# 2_classyTKL_ALPS_matrix.net
KiCad netlist of a schematic drawn in Altium Designer
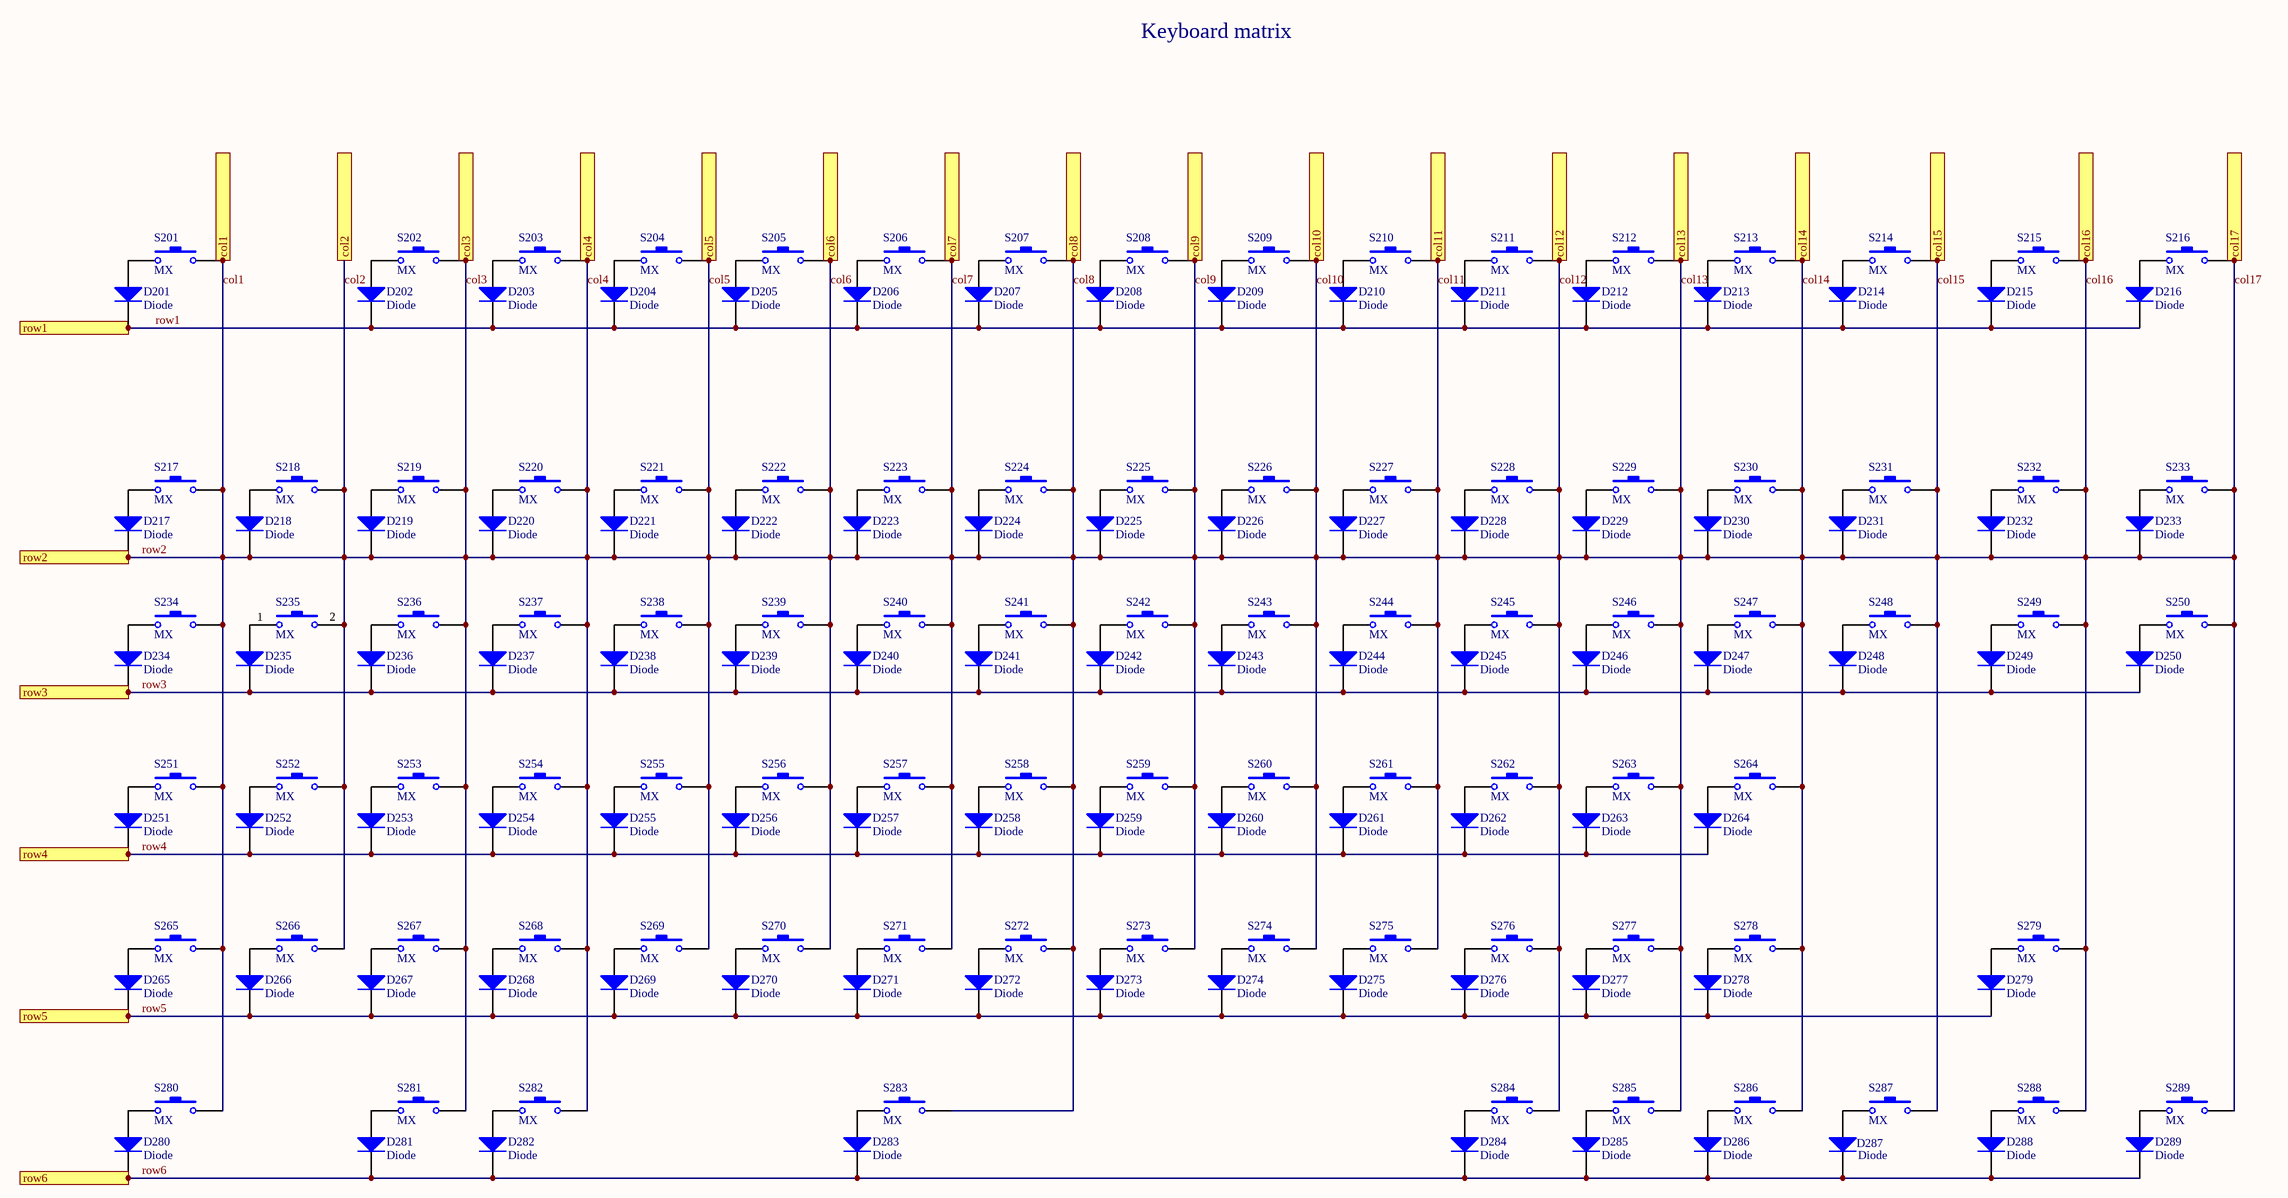
[diagram p0: 2_classyTKL_ALPS_matrix.SchDoc]

(export (version "E")
  (design (tool "Eeschema 10.0.6"))
  (components
    (comp (ref "D201")
      (value "Diode")
      (footprint "SOD-123")
      (description "Default Diode")
      (fields (field (name "LCSC PART #") "C81598") (field (name "MRF.PART") "1N4148W"))
      (libsource (lib "Miscellaneous Devices") (part "Diode"))
    )
    (comp (ref "D202")
      (value "Diode")
      (footprint "SOD-123")
      (description "Default Diode")
      (fields (field (name "LCSC PART #") "C81598") (field (name "MRF.PART") "1N4148W"))
      (libsource (lib "Miscellaneous Devices") (part "Diode"))
    )
    (comp (ref "D203")
      (value "Diode")
      (footprint "SOD-123")
      (description "Default Diode")
      (fields (field (name "LCSC PART #") "C81598") (field (name "MRF.PART") "1N4148W"))
      (libsource (lib "Miscellaneous Devices") (part "Diode"))
    )
    (comp (ref "D204")
      (value "Diode")
      (footprint "SOD-123")
      (description "Default Diode")
      (fields (field (name "LCSC PART #") "C81598") (field (name "MRF.PART") "1N4148W"))
      (libsource (lib "Miscellaneous Devices") (part "Diode"))
    )
    (comp (ref "D205")
      (value "Diode")
      (footprint "SOD-123")
      (description "Default Diode")
      (fields (field (name "LCSC PART #") "C81598") (field (name "MRF.PART") "1N4148W"))
      (libsource (lib "Miscellaneous Devices") (part "Diode"))
    )
    (comp (ref "D206")
      (value "Diode")
      (footprint "SOD-123")
      (description "Default Diode")
      (fields (field (name "LCSC PART #") "C81598") (field (name "MRF.PART") "1N4148W"))
      (libsource (lib "Miscellaneous Devices") (part "Diode"))
    )
    (comp (ref "D207")
      (value "Diode")
      (footprint "SOD-123")
      (description "Default Diode")
      (fields (field (name "LCSC PART #") "C81598") (field (name "MRF.PART") "1N4148W"))
      (libsource (lib "Miscellaneous Devices") (part "Diode"))
    )
    (comp (ref "D208")
      (value "Diode")
      (footprint "SOD-123")
      (description "Default Diode")
      (fields (field (name "LCSC PART #") "C81598") (field (name "MRF.PART") "1N4148W"))
      (libsource (lib "Miscellaneous Devices") (part "Diode"))
    )
    (comp (ref "D209")
      (value "Diode")
      (footprint "SOD-123")
      (description "Default Diode")
      (fields (field (name "LCSC PART #") "C81598") (field (name "MRF.PART") "1N4148W"))
      (libsource (lib "Miscellaneous Devices") (part "Diode"))
    )
    (comp (ref "D210")
      (value "Diode")
      (footprint "SOD-123")
      (description "Default Diode")
      (fields (field (name "LCSC PART #") "C81598") (field (name "MRF.PART") "1N4148W"))
      (libsource (lib "Miscellaneous Devices") (part "Diode"))
    )
    (comp (ref "D211")
      (value "Diode")
      (footprint "SOD-123")
      (description "Default Diode")
      (fields (field (name "LCSC PART #") "C81598") (field (name "MRF.PART") "1N4148W"))
      (libsource (lib "Miscellaneous Devices") (part "Diode"))
    )
    (comp (ref "D212")
      (value "Diode")
      (footprint "SOD-123")
      (description "Default Diode")
      (fields (field (name "LCSC PART #") "C81598") (field (name "MRF.PART") "1N4148W"))
      (libsource (lib "Miscellaneous Devices") (part "Diode"))
    )
    (comp (ref "D213")
      (value "Diode")
      (footprint "SOD-123")
      (description "Default Diode")
      (fields (field (name "LCSC PART #") "C81598") (field (name "MRF.PART") "1N4148W"))
      (libsource (lib "Miscellaneous Devices") (part "Diode"))
    )
    (comp (ref "D214")
      (value "Diode")
      (footprint "SOD-123")
      (description "Default Diode")
      (fields (field (name "LCSC PART #") "C81598") (field (name "MRF.PART") "1N4148W"))
      (libsource (lib "Miscellaneous Devices") (part "Diode"))
    )
    (comp (ref "D215")
      (value "Diode")
      (footprint "SOD-123")
      (description "Default Diode")
      (fields (field (name "LCSC PART #") "C81598") (field (name "MRF.PART") "1N4148W"))
      (libsource (lib "Miscellaneous Devices") (part "Diode"))
    )
    (comp (ref "D216")
      (value "Diode")
      (footprint "SOD-123")
      (description "Default Diode")
      (fields (field (name "LCSC PART #") "C81598") (field (name "MRF.PART") "1N4148W"))
      (libsource (lib "Miscellaneous Devices") (part "Diode"))
    )
    (comp (ref "D217")
      (value "Diode")
      (footprint "SOD-123")
      (description "Default Diode")
      (fields (field (name "LCSC PART #") "C81598") (field (name "MRF.PART") "1N4148W"))
      (libsource (lib "Miscellaneous Devices") (part "Diode"))
    )
    (comp (ref "D218")
      (value "Diode")
      (footprint "SOD-123")
      (description "Default Diode")
      (fields (field (name "LCSC PART #") "C81598") (field (name "MRF.PART") "1N4148W"))
      (libsource (lib "Miscellaneous Devices") (part "Diode"))
    )
    (comp (ref "D219")
      (value "Diode")
      (footprint "SOD-123")
      (description "Default Diode")
      (fields (field (name "LCSC PART #") "C81598") (field (name "MRF.PART") "1N4148W"))
      (libsource (lib "Miscellaneous Devices") (part "Diode"))
    )
    (comp (ref "D220")
      (value "Diode")
      (footprint "SOD-123")
      (description "Default Diode")
      (fields (field (name "LCSC PART #") "C81598") (field (name "MRF.PART") "1N4148W"))
      (libsource (lib "Miscellaneous Devices") (part "Diode"))
    )
    (comp (ref "D221")
      (value "Diode")
      (footprint "SOD-123")
      (description "Default Diode")
      (fields (field (name "LCSC PART #") "C81598") (field (name "MRF.PART") "1N4148W"))
      (libsource (lib "Miscellaneous Devices") (part "Diode"))
    )
    (comp (ref "D222")
      (value "Diode")
      (footprint "SOD-123")
      (description "Default Diode")
      (fields (field (name "LCSC PART #") "C81598") (field (name "MRF.PART") "1N4148W"))
      (libsource (lib "Miscellaneous Devices") (part "Diode"))
    )
    (comp (ref "D223")
      (value "Diode")
      (footprint "SOD-123")
      (description "Default Diode")
      (fields (field (name "LCSC PART #") "C81598") (field (name "MRF.PART") "1N4148W"))
      (libsource (lib "Miscellaneous Devices") (part "Diode"))
    )
    (comp (ref "D224")
      (value "Diode")
      (footprint "SOD-123")
      (description "Default Diode")
      (fields (field (name "LCSC PART #") "C81598") (field (name "MRF.PART") "1N4148W"))
      (libsource (lib "Miscellaneous Devices") (part "Diode"))
    )
    (comp (ref "D225")
      (value "Diode")
      (footprint "SOD-123")
      (description "Default Diode")
      (fields (field (name "LCSC PART #") "C81598") (field (name "MRF.PART") "1N4148W"))
      (libsource (lib "Miscellaneous Devices") (part "Diode"))
    )
    (comp (ref "D226")
      (value "Diode")
      (footprint "SOD-123")
      (description "Default Diode")
      (fields (field (name "LCSC PART #") "C81598") (field (name "MRF.PART") "1N4148W"))
      (libsource (lib "Miscellaneous Devices") (part "Diode"))
    )
    (comp (ref "D227")
      (value "Diode")
      (footprint "SOD-123")
      (description "Default Diode")
      (fields (field (name "LCSC PART #") "C81598") (field (name "MRF.PART") "1N4148W"))
      (libsource (lib "Miscellaneous Devices") (part "Diode"))
    )
    (comp (ref "D228")
      (value "Diode")
      (footprint "SOD-123")
      (description "Default Diode")
      (fields (field (name "LCSC PART #") "C81598") (field (name "MRF.PART") "1N4148W"))
      (libsource (lib "Miscellaneous Devices") (part "Diode"))
    )
    (comp (ref "D229")
      (value "Diode")
      (footprint "SOD-123")
      (description "Default Diode")
      (fields (field (name "LCSC PART #") "C81598") (field (name "MRF.PART") "1N4148W"))
      (libsource (lib "Miscellaneous Devices") (part "Diode"))
    )
    (comp (ref "D230")
      (value "Diode")
      (footprint "SOD-123")
      (description "Default Diode")
      (fields (field (name "LCSC PART #") "C81598") (field (name "MRF.PART") "1N4148W"))
      (libsource (lib "Miscellaneous Devices") (part "Diode"))
    )
    (comp (ref "D231")
      (value "Diode")
      (footprint "SOD-123")
      (description "Default Diode")
      (fields (field (name "LCSC PART #") "C81598") (field (name "MRF.PART") "1N4148W"))
      (libsource (lib "Miscellaneous Devices") (part "Diode"))
    )
    (comp (ref "D232")
      (value "Diode")
      (footprint "SOD-123")
      (description "Default Diode")
      (fields (field (name "LCSC PART #") "C81598") (field (name "MRF.PART") "1N4148W"))
      (libsource (lib "Miscellaneous Devices") (part "Diode"))
    )
    (comp (ref "D233")
      (value "Diode")
      (footprint "SOD-123")
      (description "Default Diode")
      (fields (field (name "LCSC PART #") "C81598") (field (name "MRF.PART") "1N4148W"))
      (libsource (lib "Miscellaneous Devices") (part "Diode"))
    )
    (comp (ref "D234")
      (value "Diode")
      (footprint "SOD-123")
      (description "Default Diode")
      (fields (field (name "LCSC PART #") "C81598") (field (name "MRF.PART") "1N4148W"))
      (libsource (lib "Miscellaneous Devices") (part "Diode"))
    )
    (comp (ref "D235")
      (value "Diode")
      (footprint "SOD-123")
      (description "Default Diode")
      (fields (field (name "LCSC PART #") "C81598") (field (name "MRF.PART") "1N4148W"))
      (libsource (lib "Miscellaneous Devices") (part "Diode"))
    )
    (comp (ref "D236")
      (value "Diode")
      (footprint "SOD-123")
      (description "Default Diode")
      (fields (field (name "LCSC PART #") "C81598") (field (name "MRF.PART") "1N4148W"))
      (libsource (lib "Miscellaneous Devices") (part "Diode"))
    )
    (comp (ref "D237")
      (value "Diode")
      (footprint "SOD-123")
      (description "Default Diode")
      (fields (field (name "LCSC PART #") "C81598") (field (name "MRF.PART") "1N4148W"))
      (libsource (lib "Miscellaneous Devices") (part "Diode"))
    )
    (comp (ref "D238")
      (value "Diode")
      (footprint "SOD-123")
      (description "Default Diode")
      (fields (field (name "LCSC PART #") "C81598") (field (name "MRF.PART") "1N4148W"))
      (libsource (lib "Miscellaneous Devices") (part "Diode"))
    )
    (comp (ref "D239")
      (value "Diode")
      (footprint "SOD-123")
      (description "Default Diode")
      (fields (field (name "LCSC PART #") "C81598") (field (name "MRF.PART") "1N4148W"))
      (libsource (lib "Miscellaneous Devices") (part "Diode"))
    )
    (comp (ref "D240")
      (value "Diode")
      (footprint "SOD-123")
      (description "Default Diode")
      (fields (field (name "LCSC PART #") "C81598") (field (name "MRF.PART") "1N4148W"))
      (libsource (lib "Miscellaneous Devices") (part "Diode"))
    )
    (comp (ref "D241")
      (value "Diode")
      (footprint "SOD-123")
      (description "Default Diode")
      (fields (field (name "LCSC PART #") "C81598") (field (name "MRF.PART") "1N4148W"))
      (libsource (lib "Miscellaneous Devices") (part "Diode"))
    )
    (comp (ref "D242")
      (value "Diode")
      (footprint "SOD-123")
      (description "Default Diode")
      (fields (field (name "LCSC PART #") "C81598") (field (name "MRF.PART") "1N4148W"))
      (libsource (lib "Miscellaneous Devices") (part "Diode"))
    )
    (comp (ref "D243")
      (value "Diode")
      (footprint "SOD-123")
      (description "Default Diode")
      (fields (field (name "LCSC PART #") "C81598") (field (name "MRF.PART") "1N4148W"))
      (libsource (lib "Miscellaneous Devices") (part "Diode"))
    )
    (comp (ref "D244")
      (value "Diode")
      (footprint "SOD-123")
      (description "Default Diode")
      (fields (field (name "LCSC PART #") "C81598") (field (name "MRF.PART") "1N4148W"))
      (libsource (lib "Miscellaneous Devices") (part "Diode"))
    )
    (comp (ref "D245")
      (value "Diode")
      (footprint "SOD-123")
      (description "Default Diode")
      (fields (field (name "LCSC PART #") "C81598") (field (name "MRF.PART") "1N4148W"))
      (libsource (lib "Miscellaneous Devices") (part "Diode"))
    )
    (comp (ref "D246")
      (value "Diode")
      (footprint "SOD-123")
      (description "Default Diode")
      (fields (field (name "LCSC PART #") "C81598") (field (name "MRF.PART") "1N4148W"))
      (libsource (lib "Miscellaneous Devices") (part "Diode"))
    )
    (comp (ref "D247")
      (value "Diode")
      (footprint "SOD-123")
      (description "Default Diode")
      (fields (field (name "LCSC PART #") "C81598") (field (name "MRF.PART") "1N4148W"))
      (libsource (lib "Miscellaneous Devices") (part "Diode"))
    )
    (comp (ref "D248")
      (value "Diode")
      (footprint "SOD-123")
      (description "Default Diode")
      (fields (field (name "LCSC PART #") "C81598") (field (name "MRF.PART") "1N4148W"))
      (libsource (lib "Miscellaneous Devices") (part "Diode"))
    )
    (comp (ref "D249")
      (value "Diode")
      (footprint "SOD-123")
      (description "Default Diode")
      (fields (field (name "LCSC PART #") "C81598") (field (name "MRF.PART") "1N4148W"))
      (libsource (lib "Miscellaneous Devices") (part "Diode"))
    )
    (comp (ref "D250")
      (value "Diode")
      (footprint "SOD-123")
      (description "Default Diode")
      (fields (field (name "LCSC PART #") "C81598") (field (name "MRF.PART") "1N4148W"))
      (libsource (lib "Miscellaneous Devices") (part "Diode"))
    )
    (comp (ref "D251")
      (value "Diode")
      (footprint "SOD-123")
      (description "Default Diode")
      (fields (field (name "LCSC PART #") "C81598") (field (name "MRF.PART") "1N4148W"))
      (libsource (lib "Miscellaneous Devices") (part "Diode"))
    )
    (comp (ref "D252")
      (value "Diode")
      (footprint "SOD-123")
      (description "Default Diode")
      (fields (field (name "LCSC PART #") "C81598") (field (name "MRF.PART") "1N4148W"))
      (libsource (lib "Miscellaneous Devices") (part "Diode"))
    )
    (comp (ref "D253")
      (value "Diode")
      (footprint "SOD-123")
      (description "Default Diode")
      (fields (field (name "LCSC PART #") "C81598") (field (name "MRF.PART") "1N4148W"))
      (libsource (lib "Miscellaneous Devices") (part "Diode"))
    )
    (comp (ref "D254")
      (value "Diode")
      (footprint "SOD-123")
      (description "Default Diode")
      (fields (field (name "LCSC PART #") "C81598") (field (name "MRF.PART") "1N4148W"))
      (libsource (lib "Miscellaneous Devices") (part "Diode"))
    )
    (comp (ref "D255")
      (value "Diode")
      (footprint "SOD-123")
      (description "Default Diode")
      (fields (field (name "LCSC PART #") "C81598") (field (name "MRF.PART") "1N4148W"))
      (libsource (lib "Miscellaneous Devices") (part "Diode"))
    )
    (comp (ref "D256")
      (value "Diode")
      (footprint "SOD-123")
      (description "Default Diode")
      (fields (field (name "LCSC PART #") "C81598") (field (name "MRF.PART") "1N4148W"))
      (libsource (lib "Miscellaneous Devices") (part "Diode"))
    )
    (comp (ref "D257")
      (value "Diode")
      (footprint "SOD-123")
      (description "Default Diode")
      (fields (field (name "LCSC PART #") "C81598") (field (name "MRF.PART") "1N4148W"))
      (libsource (lib "Miscellaneous Devices") (part "Diode"))
    )
    (comp (ref "D258")
      (value "Diode")
      (footprint "SOD-123")
      (description "Default Diode")
      (fields (field (name "LCSC PART #") "C81598") (field (name "MRF.PART") "1N4148W"))
      (libsource (lib "Miscellaneous Devices") (part "Diode"))
    )
    (comp (ref "D259")
      (value "Diode")
      (footprint "SOD-123")
      (description "Default Diode")
      (fields (field (name "LCSC PART #") "C81598") (field (name "MRF.PART") "1N4148W"))
      (libsource (lib "Miscellaneous Devices") (part "Diode"))
    )
    (comp (ref "D260")
      (value "Diode")
      (footprint "SOD-123")
      (description "Default Diode")
      (fields (field (name "LCSC PART #") "C81598") (field (name "MRF.PART") "1N4148W"))
      (libsource (lib "Miscellaneous Devices") (part "Diode"))
    )
    (comp (ref "D261")
      (value "Diode")
      (footprint "SOD-123")
      (description "Default Diode")
      (fields (field (name "LCSC PART #") "C81598") (field (name "MRF.PART") "1N4148W"))
      (libsource (lib "Miscellaneous Devices") (part "Diode"))
    )
    (comp (ref "D262")
      (value "Diode")
      (footprint "SOD-123")
      (description "Default Diode")
      (fields (field (name "LCSC PART #") "C81598") (field (name "MRF.PART") "1N4148W"))
      (libsource (lib "Miscellaneous Devices") (part "Diode"))
    )
    (comp (ref "D263")
      (value "Diode")
      (footprint "SOD-123")
      (description "Default Diode")
      (fields (field (name "LCSC PART #") "C81598") (field (name "MRF.PART") "1N4148W"))
      (libsource (lib "Miscellaneous Devices") (part "Diode"))
    )
    (comp (ref "D264")
      (value "Diode")
      (footprint "SOD-123")
      (description "Default Diode")
      (fields (field (name "LCSC PART #") "C81598") (field (name "MRF.PART") "1N4148W"))
      (libsource (lib "Miscellaneous Devices") (part "Diode"))
    )
    (comp (ref "D265")
      (value "Diode")
      (footprint "SOD-123")
      (description "Default Diode")
      (fields (field (name "LCSC PART #") "C81598") (field (name "MRF.PART") "1N4148W"))
      (libsource (lib "Miscellaneous Devices") (part "Diode"))
    )
    (comp (ref "D266")
      (value "Diode")
      (footprint "SOD-123")
      (description "Default Diode")
      (fields (field (name "LCSC PART #") "C81598") (field (name "MRF.PART") "1N4148W"))
      (libsource (lib "Miscellaneous Devices") (part "Diode"))
    )
    (comp (ref "D267")
      (value "Diode")
      (footprint "SOD-123")
      (description "Default Diode")
      (fields (field (name "LCSC PART #") "C81598") (field (name "MRF.PART") "1N4148W"))
      (libsource (lib "Miscellaneous Devices") (part "Diode"))
    )
    (comp (ref "D268")
      (value "Diode")
      (footprint "SOD-123")
      (description "Default Diode")
      (fields (field (name "LCSC PART #") "C81598") (field (name "MRF.PART") "1N4148W"))
      (libsource (lib "Miscellaneous Devices") (part "Diode"))
    )
    (comp (ref "D269")
      (value "Diode")
      (footprint "SOD-123")
      (description "Default Diode")
      (fields (field (name "LCSC PART #") "C81598") (field (name "MRF.PART") "1N4148W"))
      (libsource (lib "Miscellaneous Devices") (part "Diode"))
    )
    (comp (ref "D270")
      (value "Diode")
      (footprint "SOD-123")
      (description "Default Diode")
      (fields (field (name "LCSC PART #") "C81598") (field (name "MRF.PART") "1N4148W"))
      (libsource (lib "Miscellaneous Devices") (part "Diode"))
    )
    (comp (ref "D271")
      (value "Diode")
      (footprint "SOD-123")
      (description "Default Diode")
      (fields (field (name "LCSC PART #") "C81598") (field (name "MRF.PART") "1N4148W"))
      (libsource (lib "Miscellaneous Devices") (part "Diode"))
    )
    (comp (ref "D272")
      (value "Diode")
      (footprint "SOD-123")
      (description "Default Diode")
      (fields (field (name "LCSC PART #") "C81598") (field (name "MRF.PART") "1N4148W"))
      (libsource (lib "Miscellaneous Devices") (part "Diode"))
    )
    (comp (ref "D273")
      (value "Diode")
      (footprint "SOD-123")
      (description "Default Diode")
      (fields (field (name "LCSC PART #") "C81598") (field (name "MRF.PART") "1N4148W"))
      (libsource (lib "Miscellaneous Devices") (part "Diode"))
    )
    (comp (ref "D274")
      (value "Diode")
      (footprint "SOD-123")
      (description "Default Diode")
      (fields (field (name "LCSC PART #") "C81598") (field (name "MRF.PART") "1N4148W"))
      (libsource (lib "Miscellaneous Devices") (part "Diode"))
    )
    (comp (ref "D275")
      (value "Diode")
      (footprint "SOD-123")
      (description "Default Diode")
      (fields (field (name "LCSC PART #") "C81598") (field (name "MRF.PART") "1N4148W"))
      (libsource (lib "Miscellaneous Devices") (part "Diode"))
    )
    (comp (ref "D276")
      (value "Diode")
      (footprint "SOD-123")
      (description "Default Diode")
      (fields (field (name "LCSC PART #") "C81598") (field (name "MRF.PART") "1N4148W"))
      (libsource (lib "Miscellaneous Devices") (part "Diode"))
    )
    (comp (ref "D277")
      (value "Diode")
      (footprint "SOD-123")
      (description "Default Diode")
      (fields (field (name "LCSC PART #") "C81598") (field (name "MRF.PART") "1N4148W"))
      (libsource (lib "Miscellaneous Devices") (part "Diode"))
    )
    (comp (ref "D278")
      (value "Diode")
      (footprint "SOD-123")
      (description "Default Diode")
      (fields (field (name "LCSC PART #") "C81598") (field (name "MRF.PART") "1N4148W"))
      (libsource (lib "Miscellaneous Devices") (part "Diode"))
    )
    (comp (ref "D279")
      (value "Diode")
      (footprint "SOD-123")
      (description "Default Diode")
      (fields (field (name "LCSC PART #") "C81598") (field (name "MRF.PART") "1N4148W"))
      (libsource (lib "Miscellaneous Devices") (part "Diode"))
    )
    (comp (ref "D280")
      (value "Diode")
      (footprint "SOD-123")
      (description "Default Diode")
      (fields (field (name "LCSC PART #") "C81598") (field (name "MRF.PART") "1N4148W"))
      (libsource (lib "Miscellaneous Devices") (part "Diode"))
    )
    (comp (ref "D281")
      (value "Diode")
      (footprint "SOD-123")
      (description "Default Diode")
      (fields (field (name "LCSC PART #") "C81598") (field (name "MRF.PART") "1N4148W"))
      (libsource (lib "Miscellaneous Devices") (part "Diode"))
    )
    (comp (ref "D282")
      (value "Diode")
      (footprint "SOD-123")
      (description "Default Diode")
      (fields (field (name "LCSC PART #") "C81598") (field (name "MRF.PART") "1N4148W"))
      (libsource (lib "Miscellaneous Devices") (part "Diode"))
    )
    (comp (ref "D283")
      (value "Diode")
      (footprint "SOD-123")
      (description "Default Diode")
      (fields (field (name "LCSC PART #") "C81598") (field (name "MRF.PART") "1N4148W"))
      (libsource (lib "Miscellaneous Devices") (part "Diode"))
    )
    (comp (ref "D284")
      (value "Diode")
      (footprint "SOD-123")
      (description "Default Diode")
      (fields (field (name "LCSC PART #") "C81598") (field (name "MRF.PART") "1N4148W"))
      (libsource (lib "Miscellaneous Devices") (part "Diode"))
    )
    (comp (ref "D285")
      (value "Diode")
      (footprint "SOD-123")
      (description "Default Diode")
      (fields (field (name "LCSC PART #") "C81598") (field (name "MRF.PART") "1N4148W"))
      (libsource (lib "Miscellaneous Devices") (part "Diode"))
    )
    (comp (ref "D286")
      (value "Diode")
      (footprint "SOD-123")
      (description "Default Diode")
      (fields (field (name "LCSC PART #") "C81598") (field (name "MRF.PART") "1N4148W"))
      (libsource (lib "Miscellaneous Devices") (part "Diode"))
    )
    (comp (ref "D287")
      (value "Diode")
      (footprint "SOD-123")
      (description "Default Diode")
      (fields (field (name "LCSC PART #") "C81598") (field (name "MRF.PART") "1N4148W"))
      (libsource (lib "Miscellaneous Devices") (part "Diode"))
    )
    (comp (ref "D288")
      (value "Diode")
      (footprint "SOD-123")
      (description "Default Diode")
      (fields (field (name "LCSC PART #") "C81598") (field (name "MRF.PART") "1N4148W"))
      (libsource (lib "Miscellaneous Devices") (part "Diode"))
    )
    (comp (ref "D289")
      (value "Diode")
      (footprint "SOD-123")
      (description "Default Diode")
      (fields (field (name "LCSC PART #") "C81598") (field (name "MRF.PART") "1N4148W"))
      (libsource (lib "Miscellaneous Devices") (part "Diode"))
    )
    (comp (ref "S201")
      (value "MX")
      (footprint "Alps-switch - AEK F-row")
      (description "Switch")
      (libsource (lib "Miscellaneous Devices") (part "SW-PB"))
    )
    (comp (ref "S202")
      (value "MX")
      (footprint "Alps-switch - AEK F-row")
      (description "Switch")
      (libsource (lib "Miscellaneous Devices") (part "SW-PB"))
    )
    (comp (ref "S203")
      (value "MX")
      (footprint "Alps-switch - AEK F-row")
      (description "Switch")
      (libsource (lib "Miscellaneous Devices") (part "SW-PB"))
    )
    (comp (ref "S204")
      (value "MX")
      (footprint "Alps-switch - AEK F-row")
      (description "Switch")
      (libsource (lib "Miscellaneous Devices") (part "SW-PB"))
    )
    (comp (ref "S205")
      (value "MX")
      (footprint "Alps-switch - AEK F-row")
      (description "Switch")
      (libsource (lib "Miscellaneous Devices") (part "SW-PB"))
    )
    (comp (ref "S206")
      (value "MX")
      (footprint "Alps-switch - AEK F-row")
      (description "Switch")
      (libsource (lib "Miscellaneous Devices") (part "SW-PB"))
    )
    (comp (ref "S207")
      (value "MX")
      (footprint "Alps-switch - AEK F-row")
      (description "Switch")
      (libsource (lib "Miscellaneous Devices") (part "SW-PB"))
    )
    (comp (ref "S208")
      (value "MX")
      (footprint "Alps-switch - AEK F-row")
      (description "Switch")
      (libsource (lib "Miscellaneous Devices") (part "SW-PB"))
    )
    (comp (ref "S209")
      (value "MX")
      (footprint "Alps-switch - AEK F-row")
      (description "Switch")
      (libsource (lib "Miscellaneous Devices") (part "SW-PB"))
    )
    (comp (ref "S210")
      (value "MX")
      (footprint "Alps-switch - AEK F-row")
      (description "Switch")
      (libsource (lib "Miscellaneous Devices") (part "SW-PB"))
    )
    (comp (ref "S211")
      (value "MX")
      (footprint "Alps-switch - AEK F-row")
      (description "Switch")
      (libsource (lib "Miscellaneous Devices") (part "SW-PB"))
    )
    (comp (ref "S212")
      (value "MX")
      (footprint "Alps-switch - AEK F-row")
      (description "Switch")
      (libsource (lib "Miscellaneous Devices") (part "SW-PB"))
    )
    (comp (ref "S213")
      (value "MX")
      (footprint "Alps-switch - AEK F-row")
      (description "Switch")
      (libsource (lib "Miscellaneous Devices") (part "SW-PB"))
    )
    (comp (ref "S214")
      (value "MX")
      (footprint "Alps-switch - AEK F-row")
      (description "Switch")
      (libsource (lib "Miscellaneous Devices") (part "SW-PB"))
    )
    (comp (ref "S215")
      (value "MX")
      (footprint "Alps-switch - AEK F-row")
      (description "Switch")
      (libsource (lib "Miscellaneous Devices") (part "SW-PB"))
    )
    (comp (ref "S216")
      (value "MX")
      (footprint "Alps-switch - AEK F-row")
      (description "Switch")
      (libsource (lib "Miscellaneous Devices") (part "SW-PB"))
    )
    (comp (ref "S217")
      (value "MX")
      (footprint "Alps-switch - switched pol")
      (description "Switch")
      (libsource (lib "Miscellaneous Devices") (part "SW-PB"))
    )
    (comp (ref "S218")
      (value "MX")
      (footprint "Alps-switch - switched pol")
      (description "Switch")
      (libsource (lib "Miscellaneous Devices") (part "SW-PB"))
    )
    (comp (ref "S219")
      (value "MX")
      (footprint "Alps-switch - switched pol")
      (description "Switch")
      (libsource (lib "Miscellaneous Devices") (part "SW-PB"))
    )
    (comp (ref "S220")
      (value "MX")
      (footprint "Alps-switch - switched pol")
      (description "Switch")
      (libsource (lib "Miscellaneous Devices") (part "SW-PB"))
    )
    (comp (ref "S221")
      (value "MX")
      (footprint "Alps-switch - switched pol")
      (description "Switch")
      (libsource (lib "Miscellaneous Devices") (part "SW-PB"))
    )
    (comp (ref "S222")
      (value "MX")
      (footprint "Alps-switch - switched pol")
      (description "Switch")
      (libsource (lib "Miscellaneous Devices") (part "SW-PB"))
    )
    (comp (ref "S223")
      (value "MX")
      (footprint "Alps-switch - switched pol")
      (description "Switch")
      (libsource (lib "Miscellaneous Devices") (part "SW-PB"))
    )
    (comp (ref "S224")
      (value "MX")
      (footprint "Alps-switch - switched pol")
      (description "Switch")
      (libsource (lib "Miscellaneous Devices") (part "SW-PB"))
    )
    (comp (ref "S225")
      (value "MX")
      (footprint "Alps-switch - switched pol")
      (description "Switch")
      (libsource (lib "Miscellaneous Devices") (part "SW-PB"))
    )
    (comp (ref "S226")
      (value "MX")
      (footprint "Alps-switch - switched pol")
      (description "Switch")
      (libsource (lib "Miscellaneous Devices") (part "SW-PB"))
    )
    (comp (ref "S227")
      (value "MX")
      (footprint "Alps-switch - switched pol")
      (description "Switch")
      (libsource (lib "Miscellaneous Devices") (part "SW-PB"))
    )
    (comp (ref "S228")
      (value "MX")
      (footprint "Alps-switch - switched pol")
      (description "Switch")
      (libsource (lib "Miscellaneous Devices") (part "SW-PB"))
    )
    (comp (ref "S229")
      (value "MX")
      (footprint "Alps-switch - switched pol")
      (description "Switch")
      (libsource (lib "Miscellaneous Devices") (part "SW-PB"))
    )
    (comp (ref "S230")
      (value "MX")
      (footprint "Alps-switch")
      (description "Switch")
      (libsource (lib "Miscellaneous Devices") (part "SW-PB"))
    )
    (comp (ref "S231")
      (value "MX")
      (footprint "Alps-switch")
      (description "Switch")
      (libsource (lib "Miscellaneous Devices") (part "SW-PB"))
    )
    (comp (ref "S232")
      (value "MX")
      (footprint "Alps-switch")
      (description "Switch")
      (libsource (lib "Miscellaneous Devices") (part "SW-PB"))
    )
    (comp (ref "S233")
      (value "MX")
      (footprint "Alps-switch")
      (description "Switch")
      (libsource (lib "Miscellaneous Devices") (part "SW-PB"))
    )
    (comp (ref "S234")
      (value "MX")
      (footprint "ALPS-switch - 1.5U")
      (description "TAB")
      (libsource (lib "Miscellaneous Devices") (part "SW-PB"))
    )
    (comp (ref "S235")
      (value "MX")
      (footprint "Alps-switch - switched pol")
      (description "Switch")
      (libsource (lib "") (part "SW-PB_1"))
    )
    (comp (ref "S236")
      (value "MX")
      (footprint "Alps-switch - switched pol")
      (description "Switch")
      (libsource (lib "Miscellaneous Devices") (part "SW-PB"))
    )
    (comp (ref "S237")
      (value "MX")
      (footprint "Alps-switch - switched pol")
      (description "Switch")
      (libsource (lib "Miscellaneous Devices") (part "SW-PB"))
    )
    (comp (ref "S238")
      (value "MX")
      (footprint "Alps-switch - switched pol")
      (description "Switch")
      (libsource (lib "Miscellaneous Devices") (part "SW-PB"))
    )
    (comp (ref "S239")
      (value "MX")
      (footprint "Alps-switch - switched pol")
      (description "Switch")
      (libsource (lib "Miscellaneous Devices") (part "SW-PB"))
    )
    (comp (ref "S240")
      (value "MX")
      (footprint "Alps-switch - switched pol")
      (description "Switch")
      (libsource (lib "Miscellaneous Devices") (part "SW-PB"))
    )
    (comp (ref "S241")
      (value "MX")
      (footprint "Alps-switch - switched pol")
      (description "Switch")
      (libsource (lib "Miscellaneous Devices") (part "SW-PB"))
    )
    (comp (ref "S242")
      (value "MX")
      (footprint "Alps-switch - switched pol")
      (description "Switch")
      (libsource (lib "Miscellaneous Devices") (part "SW-PB"))
    )
    (comp (ref "S243")
      (value "MX")
      (footprint "Alps-switch - switched pol")
      (description "Switch")
      (libsource (lib "Miscellaneous Devices") (part "SW-PB"))
    )
    (comp (ref "S244")
      (value "MX")
      (footprint "Alps-switch - switched pol")
      (description "Switch")
      (libsource (lib "Miscellaneous Devices") (part "SW-PB"))
    )
    (comp (ref "S245")
      (value "MX")
      (footprint "Alps-switch - switched pol")
      (description "Switch")
      (libsource (lib "Miscellaneous Devices") (part "SW-PB"))
    )
    (comp (ref "S246")
      (value "MX")
      (footprint "Alps-switch - switched pol")
      (description "Switch")
      (libsource (lib "Miscellaneous Devices") (part "SW-PB"))
    )
    (comp (ref "S247")
      (value "MX")
      (footprint "ALPS-SWITCH - PIPE_ISO_ENTER")
      (description "Switch")
      (libsource (lib "Miscellaneous Devices") (part "SW-PB"))
    )
    (comp (ref "S248")
      (value "MX")
      (footprint "Alps-switch")
      (description "Switch")
      (libsource (lib "Miscellaneous Devices") (part "SW-PB"))
    )
    (comp (ref "S249")
      (value "MX")
      (footprint "Alps-switch")
      (description "Switch")
      (libsource (lib "Miscellaneous Devices") (part "SW-PB"))
    )
    (comp (ref "S250")
      (value "MX")
      (footprint "Alps-switch")
      (description "Switch")
      (libsource (lib "Miscellaneous Devices") (part "SW-PB"))
    )
    (comp (ref "S251")
      (value "MX")
      (footprint "ALPS-switch - CAPS")
      (description "Switch")
      (libsource (lib "Miscellaneous Devices") (part "SW-PB"))
    )
    (comp (ref "S252")
      (value "MX")
      (footprint "Alps-switch - switched pol")
      (description "Switch")
      (libsource (lib "Miscellaneous Devices") (part "SW-PB"))
    )
    (comp (ref "S253")
      (value "MX")
      (footprint "Alps-switch - switched pol")
      (description "Switch")
      (libsource (lib "Miscellaneous Devices") (part "SW-PB"))
    )
    (comp (ref "S254")
      (value "MX")
      (footprint "Alps-switch - switched pol")
      (description "Switch")
      (libsource (lib "Miscellaneous Devices") (part "SW-PB"))
    )
    (comp (ref "S255")
      (value "MX")
      (footprint "Alps-switch - switched pol")
      (description "Switch")
      (libsource (lib "Miscellaneous Devices") (part "SW-PB"))
    )
    (comp (ref "S256")
      (value "MX")
      (footprint "Alps-switch - switched pol")
      (description "Switch")
      (libsource (lib "Miscellaneous Devices") (part "SW-PB"))
    )
    (comp (ref "S257")
      (value "MX")
      (footprint "Alps-switch - switched pol")
      (description "Switch")
      (libsource (lib "Miscellaneous Devices") (part "SW-PB"))
    )
    (comp (ref "S258")
      (value "MX")
      (footprint "Alps-switch - switched pol")
      (description "Switch")
      (libsource (lib "Miscellaneous Devices") (part "SW-PB"))
    )
    (comp (ref "S259")
      (value "MX")
      (footprint "Alps-switch - switched pol")
      (description "Switch")
      (libsource (lib "Miscellaneous Devices") (part "SW-PB"))
    )
    (comp (ref "S260")
      (value "MX")
      (footprint "Alps-switch - switched pol")
      (description "Switch")
      (libsource (lib "Miscellaneous Devices") (part "SW-PB"))
    )
    (comp (ref "S261")
      (value "MX")
      (footprint "Alps-switch - switched pol")
      (description "Switch")
      (libsource (lib "Miscellaneous Devices") (part "SW-PB"))
    )
    (comp (ref "S262")
      (value "MX")
      (footprint "Alps-switch - switched pol")
      (description "Switch")
      (libsource (lib "Miscellaneous Devices") (part "SW-PB"))
    )
    (comp (ref "S263")
      (value "MX")
      (footprint "ALPS-SWITCH - ENTER_ANSI_ISO_KEY")
      (description "Switch")
      (libsource (lib "Miscellaneous Devices") (part "SW-PB"))
    )
    (comp (ref "S264")
      (value "MX")
      (footprint "ALPS-switch - backspace")
      (description "Switch")
      (libsource (lib "Miscellaneous Devices") (part "SW-PB"))
    )
    (comp (ref "S265")
      (value "MX")
      (footprint "ALPS-switch - Left shift V2")
      (description "Switch")
      (libsource (lib "Miscellaneous Devices") (part "SW-PB"))
    )
    (comp (ref "S266")
      (value "MX")
      (footprint "Alps-switch - switched pol")
      (description "Switch")
      (libsource (lib "Miscellaneous Devices") (part "SW-PB"))
    )
    (comp (ref "S267")
      (value "MX")
      (footprint "Alps-switch - switched pol")
      (description "Switch")
      (libsource (lib "Miscellaneous Devices") (part "SW-PB"))
    )
    (comp (ref "S268")
      (value "MX")
      (footprint "Alps-switch - switched pol")
      (description "Switch")
      (libsource (lib "Miscellaneous Devices") (part "SW-PB"))
    )
    (comp (ref "S269")
      (value "MX")
      (footprint "Alps-switch - switched pol")
      (description "Switch")
      (libsource (lib "Miscellaneous Devices") (part "SW-PB"))
    )
    (comp (ref "S270")
      (value "MX")
      (footprint "Alps-switch - switched pol")
      (description "Switch")
      (libsource (lib "Miscellaneous Devices") (part "SW-PB"))
    )
    (comp (ref "S271")
      (value "MX")
      (footprint "Alps-switch - switched pol")
      (description "Switch")
      (libsource (lib "Miscellaneous Devices") (part "SW-PB"))
    )
    (comp (ref "S272")
      (value "MX")
      (footprint "Alps-switch - switched pol")
      (description "Switch")
      (libsource (lib "Miscellaneous Devices") (part "SW-PB"))
    )
    (comp (ref "S273")
      (value "MX")
      (footprint "Alps-switch - switched pol")
      (description "Switch")
      (libsource (lib "Miscellaneous Devices") (part "SW-PB"))
    )
    (comp (ref "S274")
      (value "MX")
      (footprint "Alps-switch - switched pol")
      (description "Switch")
      (libsource (lib "Miscellaneous Devices") (part "SW-PB"))
    )
    (comp (ref "S275")
      (value "MX")
      (footprint "Alps-switch - switched pol")
      (description "Switch")
      (libsource (lib "Miscellaneous Devices") (part "SW-PB"))
    )
    (comp (ref "S276")
      (value "MX")
      (footprint "Alps-switch - switched pol")
      (description "Switch")
      (libsource (lib "Miscellaneous Devices") (part "SW-PB"))
    )
    (comp (ref "S277")
      (value "MX")
      (footprint "ALPS-switch - right shift V2")
      (description "Switch")
      (libsource (lib "Miscellaneous Devices") (part "SW-PB"))
    )
    (comp (ref "S278")
      (value "MX")
      (footprint "Alps-switch - switched pol")
      (description "Switch")
      (libsource (lib "Miscellaneous Devices") (part "SW-PB"))
    )
    (comp (ref "S279")
      (value "MX")
      (footprint "Alps-switch")
      (description "Switch")
      (libsource (lib "Miscellaneous Devices") (part "SW-PB"))
    )
    (comp (ref "S280")
      (value "MX")
      (footprint "ALPS-switch - 1.5U")
      (description "Switch")
      (libsource (lib "Miscellaneous Devices") (part "SW-PB"))
    )
    (comp (ref "S281")
      (value "MX")
      (footprint "Alps-switch")
      (description "Switch")
      (libsource (lib "Miscellaneous Devices") (part "SW-PB"))
    )
    (comp (ref "S282")
      (value "MX")
      (footprint "ALPS-switch - 1.5U")
      (description "Switch")
      (libsource (lib "Miscellaneous Devices") (part "SW-PB"))
    )
    (comp (ref "S283")
      (value "MX")
      (footprint "ALPS-switch - 7u space")
      (description "Switch")
      (libsource (lib "Miscellaneous Devices") (part "SW-PB"))
    )
    (comp (ref "S284")
      (value "MX")
      (footprint "ALPS-switch - 1.5U")
      (description "Switch")
      (libsource (lib "Miscellaneous Devices") (part "SW-PB"))
    )
    (comp (ref "S285")
      (value "MX")
      (footprint "Alps-switch")
      (description "Switch")
      (libsource (lib "Miscellaneous Devices") (part "SW-PB"))
    )
    (comp (ref "S286")
      (value "MX")
      (footprint "ALPS-switch - 1.5U")
      (description "Switch")
      (libsource (lib "Miscellaneous Devices") (part "SW-PB"))
    )
    (comp (ref "S287")
      (value "MX")
      (footprint "Alps-switch")
      (description "Switch")
      (libsource (lib "Miscellaneous Devices") (part "SW-PB"))
    )
    (comp (ref "S288")
      (value "MX")
      (footprint "Alps-switch")
      (description "Switch")
      (libsource (lib "Miscellaneous Devices") (part "SW-PB"))
    )
    (comp (ref "S289")
      (value "MX")
      (footprint "Alps-switch")
      (description "Switch")
      (libsource (lib "Miscellaneous Devices") (part "SW-PB"))
    )
  )
  (nets
    (net (code "1") (name "/col1") (class "Default")
      (node (ref "D217") (pin "2") (pinfunction "K_2") (pintype "passive"))
      (node (ref "D218") (pin "2") (pinfunction "K_2") (pintype "passive"))
      (node (ref "D219") (pin "2") (pinfunction "K_2") (pintype "passive"))
      (node (ref "D220") (pin "2") (pinfunction "K_2") (pintype "passive"))
      (node (ref "D221") (pin "2") (pinfunction "K_2") (pintype "passive"))
      (node (ref "D222") (pin "2") (pinfunction "K_2") (pintype "passive"))
      (node (ref "D223") (pin "2") (pinfunction "K_2") (pintype "passive"))
      (node (ref "D224") (pin "2") (pinfunction "K_2") (pintype "passive"))
      (node (ref "D225") (pin "2") (pinfunction "K_2") (pintype "passive"))
      (node (ref "D226") (pin "2") (pinfunction "K_2") (pintype "passive"))
      (node (ref "D227") (pin "2") (pinfunction "K_2") (pintype "passive"))
      (node (ref "D228") (pin "2") (pinfunction "K_2") (pintype "passive"))
      (node (ref "D229") (pin "2") (pinfunction "K_2") (pintype "passive"))
      (node (ref "D230") (pin "2") (pinfunction "K_2") (pintype "passive"))
      (node (ref "D231") (pin "2") (pinfunction "K_2") (pintype "passive"))
      (node (ref "D232") (pin "2") (pinfunction "K_2") (pintype "passive"))
      (node (ref "D233") (pin "2") (pinfunction "K_2") (pintype "passive"))
      (node (ref "S201") (pin "2") (pinfunction "2_2") (pintype "passive"))
      (node (ref "S202") (pin "2") (pinfunction "2_2") (pintype "passive"))
      (node (ref "S203") (pin "2") (pinfunction "2_2") (pintype "passive"))
      (node (ref "S204") (pin "2") (pinfunction "2_2") (pintype "passive"))
      (node (ref "S205") (pin "2") (pinfunction "2_2") (pintype "passive"))
      (node (ref "S206") (pin "2") (pinfunction "2_2") (pintype "passive"))
      (node (ref "S207") (pin "2") (pinfunction "2_2") (pintype "passive"))
      (node (ref "S208") (pin "2") (pinfunction "2_2") (pintype "passive"))
      (node (ref "S209") (pin "2") (pinfunction "2_2") (pintype "passive"))
      (node (ref "S210") (pin "2") (pinfunction "2_2") (pintype "passive"))
      (node (ref "S211") (pin "2") (pinfunction "2_2") (pintype "passive"))
      (node (ref "S212") (pin "2") (pinfunction "2_2") (pintype "passive"))
      (node (ref "S213") (pin "2") (pinfunction "2_2") (pintype "passive"))
      (node (ref "S214") (pin "2") (pinfunction "2_2") (pintype "passive"))
      (node (ref "S215") (pin "2") (pinfunction "2_2") (pintype "passive"))
      (node (ref "S216") (pin "2") (pinfunction "2_2") (pintype "passive"))
      (node (ref "S217") (pin "2") (pinfunction "2_2") (pintype "passive"))
      (node (ref "S218") (pin "2") (pinfunction "2_2") (pintype "passive"))
      (node (ref "S219") (pin "2") (pinfunction "2_2") (pintype "passive"))
      (node (ref "S220") (pin "2") (pinfunction "2_2") (pintype "passive"))
      (node (ref "S221") (pin "2") (pinfunction "2_2") (pintype "passive"))
      (node (ref "S222") (pin "2") (pinfunction "2_2") (pintype "passive"))
      (node (ref "S223") (pin "2") (pinfunction "2_2") (pintype "passive"))
      (node (ref "S224") (pin "2") (pinfunction "2_2") (pintype "passive"))
      (node (ref "S225") (pin "2") (pinfunction "2_2") (pintype "passive"))
      (node (ref "S226") (pin "2") (pinfunction "2_2") (pintype "passive"))
      (node (ref "S227") (pin "2") (pinfunction "2_2") (pintype "passive"))
      (node (ref "S228") (pin "2") (pinfunction "2_2") (pintype "passive"))
      (node (ref "S229") (pin "2") (pinfunction "2_2") (pintype "passive"))
      (node (ref "S230") (pin "2") (pinfunction "2_2") (pintype "passive"))
      (node (ref "S231") (pin "2") (pinfunction "2_2") (pintype "passive"))
      (node (ref "S232") (pin "2") (pinfunction "2_2") (pintype "passive"))
      (node (ref "S233") (pin "2") (pinfunction "2_2") (pintype "passive"))
      (node (ref "S234") (pin "2") (pinfunction "2_2") (pintype "passive"))
      (node (ref "S235") (pin "2") (pinfunction "2_2") (pintype "passive"))
      (node (ref "S236") (pin "2") (pinfunction "2_2") (pintype "passive"))
      (node (ref "S237") (pin "2") (pinfunction "2_2") (pintype "passive"))
      (node (ref "S238") (pin "2") (pinfunction "2_2") (pintype "passive"))
      (node (ref "S239") (pin "2") (pinfunction "2_2") (pintype "passive"))
      (node (ref "S240") (pin "2") (pinfunction "2_2") (pintype "passive"))
      (node (ref "S241") (pin "2") (pinfunction "2_2") (pintype "passive"))
      (node (ref "S242") (pin "2") (pinfunction "2_2") (pintype "passive"))
      (node (ref "S243") (pin "2") (pinfunction "2_2") (pintype "passive"))
      (node (ref "S244") (pin "2") (pinfunction "2_2") (pintype "passive"))
      (node (ref "S245") (pin "2") (pinfunction "2_2") (pintype "passive"))
      (node (ref "S246") (pin "2") (pinfunction "2_2") (pintype "passive"))
      (node (ref "S247") (pin "2") (pinfunction "2_2") (pintype "passive"))
      (node (ref "S248") (pin "2") (pinfunction "2_2") (pintype "passive"))
      (node (ref "S249") (pin "2") (pinfunction "2_2") (pintype "passive"))
      (node (ref "S250") (pin "2") (pinfunction "2_2") (pintype "passive"))
      (node (ref "S251") (pin "2") (pinfunction "2_2") (pintype "passive"))
      (node (ref "S252") (pin "2") (pinfunction "2_2") (pintype "passive"))
      (node (ref "S253") (pin "2") (pinfunction "2_2") (pintype "passive"))
      (node (ref "S254") (pin "2") (pinfunction "2_2") (pintype "passive"))
      (node (ref "S255") (pin "2") (pinfunction "2_2") (pintype "passive"))
      (node (ref "S256") (pin "2") (pinfunction "2_2") (pintype "passive"))
      (node (ref "S257") (pin "2") (pinfunction "2_2") (pintype "passive"))
      (node (ref "S258") (pin "2") (pinfunction "2_2") (pintype "passive"))
      (node (ref "S259") (pin "2") (pinfunction "2_2") (pintype "passive"))
      (node (ref "S260") (pin "2") (pinfunction "2_2") (pintype "passive"))
      (node (ref "S261") (pin "2") (pinfunction "2_2") (pintype "passive"))
      (node (ref "S262") (pin "2") (pinfunction "2_2") (pintype "passive"))
      (node (ref "S263") (pin "2") (pinfunction "2_2") (pintype "passive"))
      (node (ref "S264") (pin "2") (pinfunction "2_2") (pintype "passive"))
      (node (ref "S265") (pin "2") (pinfunction "2_2") (pintype "passive"))
      (node (ref "S266") (pin "2") (pinfunction "2_2") (pintype "passive"))
      (node (ref "S267") (pin "2") (pinfunction "2_2") (pintype "passive"))
      (node (ref "S268") (pin "2") (pinfunction "2_2") (pintype "passive"))
      (node (ref "S269") (pin "2") (pinfunction "2_2") (pintype "passive"))
      (node (ref "S270") (pin "2") (pinfunction "2_2") (pintype "passive"))
      (node (ref "S271") (pin "2") (pinfunction "2_2") (pintype "passive"))
      (node (ref "S272") (pin "2") (pinfunction "2_2") (pintype "passive"))
      (node (ref "S273") (pin "2") (pinfunction "2_2") (pintype "passive"))
      (node (ref "S274") (pin "2") (pinfunction "2_2") (pintype "passive"))
      (node (ref "S275") (pin "2") (pinfunction "2_2") (pintype "passive"))
      (node (ref "S276") (pin "2") (pinfunction "2_2") (pintype "passive"))
      (node (ref "S277") (pin "2") (pinfunction "2_2") (pintype "passive"))
      (node (ref "S278") (pin "2") (pinfunction "2_2") (pintype "passive"))
      (node (ref "S279") (pin "2") (pinfunction "2_2") (pintype "passive"))
      (node (ref "S280") (pin "2") (pinfunction "2_2") (pintype "passive"))
      (node (ref "S281") (pin "2") (pinfunction "2_2") (pintype "passive"))
      (node (ref "S282") (pin "2") (pinfunction "2_2") (pintype "passive"))
      (node (ref "S283") (pin "2") (pinfunction "2_2") (pintype "passive"))
      (node (ref "S284") (pin "2") (pinfunction "2_2") (pintype "passive"))
      (node (ref "S285") (pin "2") (pinfunction "2_2") (pintype "passive"))
      (node (ref "S286") (pin "2") (pinfunction "2_2") (pintype "passive"))
      (node (ref "S287") (pin "2") (pinfunction "2_2") (pintype "passive"))
      (node (ref "S288") (pin "2") (pinfunction "2_2") (pintype "passive"))
      (node (ref "S289") (pin "2") (pinfunction "2_2") (pintype "passive"))
    )
    (net (code "2") (name "/row1") (class "Default")
      (node (ref "D201") (pin "2") (pinfunction "K_2") (pintype "passive"))
      (node (ref "D202") (pin "2") (pinfunction "K_2") (pintype "passive"))
      (node (ref "D203") (pin "2") (pinfunction "K_2") (pintype "passive"))
      (node (ref "D204") (pin "2") (pinfunction "K_2") (pintype "passive"))
      (node (ref "D205") (pin "2") (pinfunction "K_2") (pintype "passive"))
      (node (ref "D206") (pin "2") (pinfunction "K_2") (pintype "passive"))
      (node (ref "D207") (pin "2") (pinfunction "K_2") (pintype "passive"))
      (node (ref "D208") (pin "2") (pinfunction "K_2") (pintype "passive"))
      (node (ref "D209") (pin "2") (pinfunction "K_2") (pintype "passive"))
      (node (ref "D210") (pin "2") (pinfunction "K_2") (pintype "passive"))
      (node (ref "D211") (pin "2") (pinfunction "K_2") (pintype "passive"))
      (node (ref "D212") (pin "2") (pinfunction "K_2") (pintype "passive"))
      (node (ref "D213") (pin "2") (pinfunction "K_2") (pintype "passive"))
      (node (ref "D214") (pin "2") (pinfunction "K_2") (pintype "passive"))
      (node (ref "D215") (pin "2") (pinfunction "K_2") (pintype "passive"))
      (node (ref "D216") (pin "2") (pinfunction "K_2") (pintype "passive"))
    )
    (net (code "3") (name "/row3") (class "Default")
      (node (ref "D234") (pin "2") (pinfunction "K_2") (pintype "passive"))
      (node (ref "D235") (pin "2") (pinfunction "K_2") (pintype "passive"))
      (node (ref "D236") (pin "2") (pinfunction "K_2") (pintype "passive"))
      (node (ref "D237") (pin "2") (pinfunction "K_2") (pintype "passive"))
      (node (ref "D238") (pin "2") (pinfunction "K_2") (pintype "passive"))
      (node (ref "D239") (pin "2") (pinfunction "K_2") (pintype "passive"))
      (node (ref "D240") (pin "2") (pinfunction "K_2") (pintype "passive"))
      (node (ref "D241") (pin "2") (pinfunction "K_2") (pintype "passive"))
      (node (ref "D242") (pin "2") (pinfunction "K_2") (pintype "passive"))
      (node (ref "D243") (pin "2") (pinfunction "K_2") (pintype "passive"))
      (node (ref "D244") (pin "2") (pinfunction "K_2") (pintype "passive"))
      (node (ref "D245") (pin "2") (pinfunction "K_2") (pintype "passive"))
      (node (ref "D246") (pin "2") (pinfunction "K_2") (pintype "passive"))
      (node (ref "D247") (pin "2") (pinfunction "K_2") (pintype "passive"))
      (node (ref "D248") (pin "2") (pinfunction "K_2") (pintype "passive"))
      (node (ref "D249") (pin "2") (pinfunction "K_2") (pintype "passive"))
      (node (ref "D250") (pin "2") (pinfunction "K_2") (pintype "passive"))
    )
    (net (code "4") (name "/row4") (class "Default")
      (node (ref "D251") (pin "2") (pinfunction "K_2") (pintype "passive"))
      (node (ref "D252") (pin "2") (pinfunction "K_2") (pintype "passive"))
      (node (ref "D253") (pin "2") (pinfunction "K_2") (pintype "passive"))
      (node (ref "D254") (pin "2") (pinfunction "K_2") (pintype "passive"))
      (node (ref "D255") (pin "2") (pinfunction "K_2") (pintype "passive"))
      (node (ref "D256") (pin "2") (pinfunction "K_2") (pintype "passive"))
      (node (ref "D257") (pin "2") (pinfunction "K_2") (pintype "passive"))
      (node (ref "D258") (pin "2") (pinfunction "K_2") (pintype "passive"))
      (node (ref "D259") (pin "2") (pinfunction "K_2") (pintype "passive"))
      (node (ref "D260") (pin "2") (pinfunction "K_2") (pintype "passive"))
      (node (ref "D261") (pin "2") (pinfunction "K_2") (pintype "passive"))
      (node (ref "D262") (pin "2") (pinfunction "K_2") (pintype "passive"))
      (node (ref "D263") (pin "2") (pinfunction "K_2") (pintype "passive"))
      (node (ref "D264") (pin "2") (pinfunction "K_2") (pintype "passive"))
    )
    (net (code "5") (name "/row5") (class "Default")
      (node (ref "D265") (pin "2") (pinfunction "K_2") (pintype "passive"))
      (node (ref "D266") (pin "2") (pinfunction "K_2") (pintype "passive"))
      (node (ref "D267") (pin "2") (pinfunction "K_2") (pintype "passive"))
      (node (ref "D268") (pin "2") (pinfunction "K_2") (pintype "passive"))
      (node (ref "D269") (pin "2") (pinfunction "K_2") (pintype "passive"))
      (node (ref "D270") (pin "2") (pinfunction "K_2") (pintype "passive"))
      (node (ref "D271") (pin "2") (pinfunction "K_2") (pintype "passive"))
      (node (ref "D272") (pin "2") (pinfunction "K_2") (pintype "passive"))
      (node (ref "D273") (pin "2") (pinfunction "K_2") (pintype "passive"))
      (node (ref "D274") (pin "2") (pinfunction "K_2") (pintype "passive"))
      (node (ref "D275") (pin "2") (pinfunction "K_2") (pintype "passive"))
      (node (ref "D276") (pin "2") (pinfunction "K_2") (pintype "passive"))
      (node (ref "D277") (pin "2") (pinfunction "K_2") (pintype "passive"))
      (node (ref "D278") (pin "2") (pinfunction "K_2") (pintype "passive"))
      (node (ref "D279") (pin "2") (pinfunction "K_2") (pintype "passive"))
    )
    (net (code "6") (name "/row6") (class "Default")
      (node (ref "D280") (pin "2") (pinfunction "K_2") (pintype "passive"))
      (node (ref "D281") (pin "2") (pinfunction "K_2") (pintype "passive"))
      (node (ref "D282") (pin "2") (pinfunction "K_2") (pintype "passive"))
      (node (ref "D283") (pin "2") (pinfunction "K_2") (pintype "passive"))
      (node (ref "D284") (pin "2") (pinfunction "K_2") (pintype "passive"))
      (node (ref "D285") (pin "2") (pinfunction "K_2") (pintype "passive"))
      (node (ref "D286") (pin "2") (pinfunction "K_2") (pintype "passive"))
      (node (ref "D287") (pin "2") (pinfunction "K_2") (pintype "passive"))
      (node (ref "D288") (pin "2") (pinfunction "K_2") (pintype "passive"))
      (node (ref "D289") (pin "2") (pinfunction "K_2") (pintype "passive"))
    )
    (net (code "7") (name "Net-(D201-A)") (class "Default")
      (node (ref "D201") (pin "1") (pinfunction "A_1") (pintype "passive"))
      (node (ref "S201") (pin "1") (pinfunction "1_1") (pintype "passive"))
    )
    (net (code "8") (name "Net-(D202-A)") (class "Default")
      (node (ref "D202") (pin "1") (pinfunction "A_1") (pintype "passive"))
      (node (ref "S202") (pin "1") (pinfunction "1_1") (pintype "passive"))
    )
    (net (code "9") (name "Net-(D203-A)") (class "Default")
      (node (ref "D203") (pin "1") (pinfunction "A_1") (pintype "passive"))
      (node (ref "S203") (pin "1") (pinfunction "1_1") (pintype "passive"))
    )
    (net (code "10") (name "Net-(D204-A)") (class "Default")
      (node (ref "D204") (pin "1") (pinfunction "A_1") (pintype "passive"))
      (node (ref "S204") (pin "1") (pinfunction "1_1") (pintype "passive"))
    )
    (net (code "11") (name "Net-(D205-A)") (class "Default")
      (node (ref "D205") (pin "1") (pinfunction "A_1") (pintype "passive"))
      (node (ref "S205") (pin "1") (pinfunction "1_1") (pintype "passive"))
    )
    (net (code "12") (name "Net-(D206-A)") (class "Default")
      (node (ref "D206") (pin "1") (pinfunction "A_1") (pintype "passive"))
      (node (ref "S206") (pin "1") (pinfunction "1_1") (pintype "passive"))
    )
    (net (code "13") (name "Net-(D207-A)") (class "Default")
      (node (ref "D207") (pin "1") (pinfunction "A_1") (pintype "passive"))
      (node (ref "S207") (pin "1") (pinfunction "1_1") (pintype "passive"))
    )
    (net (code "14") (name "Net-(D208-A)") (class "Default")
      (node (ref "D208") (pin "1") (pinfunction "A_1") (pintype "passive"))
      (node (ref "S208") (pin "1") (pinfunction "1_1") (pintype "passive"))
    )
    (net (code "15") (name "Net-(D209-A)") (class "Default")
      (node (ref "D209") (pin "1") (pinfunction "A_1") (pintype "passive"))
      (node (ref "S209") (pin "1") (pinfunction "1_1") (pintype "passive"))
    )
    (net (code "16") (name "Net-(D210-A)") (class "Default")
      (node (ref "D210") (pin "1") (pinfunction "A_1") (pintype "passive"))
      (node (ref "S210") (pin "1") (pinfunction "1_1") (pintype "passive"))
    )
    (net (code "17") (name "Net-(D211-A)") (class "Default")
      (node (ref "D211") (pin "1") (pinfunction "A_1") (pintype "passive"))
      (node (ref "S211") (pin "1") (pinfunction "1_1") (pintype "passive"))
    )
    (net (code "18") (name "Net-(D212-A)") (class "Default")
      (node (ref "D212") (pin "1") (pinfunction "A_1") (pintype "passive"))
      (node (ref "S212") (pin "1") (pinfunction "1_1") (pintype "passive"))
    )
    (net (code "19") (name "Net-(D213-A)") (class "Default")
      (node (ref "D213") (pin "1") (pinfunction "A_1") (pintype "passive"))
      (node (ref "S213") (pin "1") (pinfunction "1_1") (pintype "passive"))
    )
    (net (code "20") (name "Net-(D214-A)") (class "Default")
      (node (ref "D214") (pin "1") (pinfunction "A_1") (pintype "passive"))
      (node (ref "S214") (pin "1") (pinfunction "1_1") (pintype "passive"))
    )
    (net (code "21") (name "Net-(D215-A)") (class "Default")
      (node (ref "D215") (pin "1") (pinfunction "A_1") (pintype "passive"))
      (node (ref "S215") (pin "1") (pinfunction "1_1") (pintype "passive"))
    )
    (net (code "22") (name "Net-(D216-A)") (class "Default")
      (node (ref "D216") (pin "1") (pinfunction "A_1") (pintype "passive"))
      (node (ref "S216") (pin "1") (pinfunction "1_1") (pintype "passive"))
    )
    (net (code "23") (name "Net-(D217-A)") (class "Default")
      (node (ref "D217") (pin "1") (pinfunction "A_1") (pintype "passive"))
      (node (ref "S217") (pin "1") (pinfunction "1_1") (pintype "passive"))
    )
    (net (code "24") (name "Net-(D218-A)") (class "Default")
      (node (ref "D218") (pin "1") (pinfunction "A_1") (pintype "passive"))
      (node (ref "S218") (pin "1") (pinfunction "1_1") (pintype "passive"))
    )
    (net (code "25") (name "Net-(D219-A)") (class "Default")
      (node (ref "D219") (pin "1") (pinfunction "A_1") (pintype "passive"))
      (node (ref "S219") (pin "1") (pinfunction "1_1") (pintype "passive"))
    )
    (net (code "26") (name "Net-(D220-A)") (class "Default")
      (node (ref "D220") (pin "1") (pinfunction "A_1") (pintype "passive"))
      (node (ref "S220") (pin "1") (pinfunction "1_1") (pintype "passive"))
    )
    (net (code "27") (name "Net-(D221-A)") (class "Default")
      (node (ref "D221") (pin "1") (pinfunction "A_1") (pintype "passive"))
      (node (ref "S221") (pin "1") (pinfunction "1_1") (pintype "passive"))
    )
    (net (code "28") (name "Net-(D222-A)") (class "Default")
      (node (ref "D222") (pin "1") (pinfunction "A_1") (pintype "passive"))
      (node (ref "S222") (pin "1") (pinfunction "1_1") (pintype "passive"))
    )
    (net (code "29") (name "Net-(D223-A)") (class "Default")
      (node (ref "D223") (pin "1") (pinfunction "A_1") (pintype "passive"))
      (node (ref "S223") (pin "1") (pinfunction "1_1") (pintype "passive"))
    )
    (net (code "30") (name "Net-(D224-A)") (class "Default")
      (node (ref "D224") (pin "1") (pinfunction "A_1") (pintype "passive"))
      (node (ref "S224") (pin "1") (pinfunction "1_1") (pintype "passive"))
    )
    (net (code "31") (name "Net-(D225-A)") (class "Default")
      (node (ref "D225") (pin "1") (pinfunction "A_1") (pintype "passive"))
      (node (ref "S225") (pin "1") (pinfunction "1_1") (pintype "passive"))
    )
    (net (code "32") (name "Net-(D226-A)") (class "Default")
      (node (ref "D226") (pin "1") (pinfunction "A_1") (pintype "passive"))
      (node (ref "S226") (pin "1") (pinfunction "1_1") (pintype "passive"))
    )
    (net (code "33") (name "Net-(D227-A)") (class "Default")
      (node (ref "D227") (pin "1") (pinfunction "A_1") (pintype "passive"))
      (node (ref "S227") (pin "1") (pinfunction "1_1") (pintype "passive"))
    )
    (net (code "34") (name "Net-(D228-A)") (class "Default")
      (node (ref "D228") (pin "1") (pinfunction "A_1") (pintype "passive"))
      (node (ref "S228") (pin "1") (pinfunction "1_1") (pintype "passive"))
    )
    (net (code "35") (name "Net-(D229-A)") (class "Default")
      (node (ref "D229") (pin "1") (pinfunction "A_1") (pintype "passive"))
      (node (ref "S229") (pin "1") (pinfunction "1_1") (pintype "passive"))
    )
    (net (code "36") (name "Net-(D230-A)") (class "Default")
      (node (ref "D230") (pin "1") (pinfunction "A_1") (pintype "passive"))
      (node (ref "S230") (pin "1") (pinfunction "1_1") (pintype "passive"))
    )
    (net (code "37") (name "Net-(D231-A)") (class "Default")
      (node (ref "D231") (pin "1") (pinfunction "A_1") (pintype "passive"))
      (node (ref "S231") (pin "1") (pinfunction "1_1") (pintype "passive"))
    )
    (net (code "38") (name "Net-(D232-A)") (class "Default")
      (node (ref "D232") (pin "1") (pinfunction "A_1") (pintype "passive"))
      (node (ref "S232") (pin "1") (pinfunction "1_1") (pintype "passive"))
    )
    (net (code "39") (name "Net-(D233-A)") (class "Default")
      (node (ref "D233") (pin "1") (pinfunction "A_1") (pintype "passive"))
      (node (ref "S233") (pin "1") (pinfunction "1_1") (pintype "passive"))
    )
    (net (code "40") (name "Net-(D234-A)") (class "Default")
      (node (ref "D234") (pin "1") (pinfunction "A_1") (pintype "passive"))
      (node (ref "S234") (pin "1") (pinfunction "1_1") (pintype "passive"))
    )
    (net (code "41") (name "Net-(D235-A)") (class "Default")
      (node (ref "D235") (pin "1") (pinfunction "A_1") (pintype "passive"))
      (node (ref "S235") (pin "1") (pinfunction "1_1") (pintype "passive"))
    )
    (net (code "42") (name "Net-(D236-A)") (class "Default")
      (node (ref "D236") (pin "1") (pinfunction "A_1") (pintype "passive"))
      (node (ref "S236") (pin "1") (pinfunction "1_1") (pintype "passive"))
    )
    (net (code "43") (name "Net-(D237-A)") (class "Default")
      (node (ref "D237") (pin "1") (pinfunction "A_1") (pintype "passive"))
      (node (ref "S237") (pin "1") (pinfunction "1_1") (pintype "passive"))
    )
    (net (code "44") (name "Net-(D238-A)") (class "Default")
      (node (ref "D238") (pin "1") (pinfunction "A_1") (pintype "passive"))
      (node (ref "S238") (pin "1") (pinfunction "1_1") (pintype "passive"))
    )
    (net (code "45") (name "Net-(D239-A)") (class "Default")
      (node (ref "D239") (pin "1") (pinfunction "A_1") (pintype "passive"))
      (node (ref "S239") (pin "1") (pinfunction "1_1") (pintype "passive"))
    )
    (net (code "46") (name "Net-(D240-A)") (class "Default")
      (node (ref "D240") (pin "1") (pinfunction "A_1") (pintype "passive"))
      (node (ref "S240") (pin "1") (pinfunction "1_1") (pintype "passive"))
    )
    (net (code "47") (name "Net-(D241-A)") (class "Default")
      (node (ref "D241") (pin "1") (pinfunction "A_1") (pintype "passive"))
      (node (ref "S241") (pin "1") (pinfunction "1_1") (pintype "passive"))
    )
    (net (code "48") (name "Net-(D242-A)") (class "Default")
      (node (ref "D242") (pin "1") (pinfunction "A_1") (pintype "passive"))
      (node (ref "S242") (pin "1") (pinfunction "1_1") (pintype "passive"))
    )
    (net (code "49") (name "Net-(D243-A)") (class "Default")
      (node (ref "D243") (pin "1") (pinfunction "A_1") (pintype "passive"))
      (node (ref "S243") (pin "1") (pinfunction "1_1") (pintype "passive"))
    )
    (net (code "50") (name "Net-(D244-A)") (class "Default")
      (node (ref "D244") (pin "1") (pinfunction "A_1") (pintype "passive"))
      (node (ref "S244") (pin "1") (pinfunction "1_1") (pintype "passive"))
    )
    (net (code "51") (name "Net-(D245-A)") (class "Default")
      (node (ref "D245") (pin "1") (pinfunction "A_1") (pintype "passive"))
      (node (ref "S245") (pin "1") (pinfunction "1_1") (pintype "passive"))
    )
    (net (code "52") (name "Net-(D246-A)") (class "Default")
      (node (ref "D246") (pin "1") (pinfunction "A_1") (pintype "passive"))
      (node (ref "S246") (pin "1") (pinfunction "1_1") (pintype "passive"))
    )
    (net (code "53") (name "Net-(D247-A)") (class "Default")
      (node (ref "D247") (pin "1") (pinfunction "A_1") (pintype "passive"))
      (node (ref "S247") (pin "1") (pinfunction "1_1") (pintype "passive"))
    )
    (net (code "54") (name "Net-(D248-A)") (class "Default")
      (node (ref "D248") (pin "1") (pinfunction "A_1") (pintype "passive"))
      (node (ref "S248") (pin "1") (pinfunction "1_1") (pintype "passive"))
    )
    (net (code "55") (name "Net-(D249-A)") (class "Default")
      (node (ref "D249") (pin "1") (pinfunction "A_1") (pintype "passive"))
      (node (ref "S249") (pin "1") (pinfunction "1_1") (pintype "passive"))
    )
    (net (code "56") (name "Net-(D250-A)") (class "Default")
      (node (ref "D250") (pin "1") (pinfunction "A_1") (pintype "passive"))
      (node (ref "S250") (pin "1") (pinfunction "1_1") (pintype "passive"))
    )
    (net (code "57") (name "Net-(D251-A)") (class "Default")
      (node (ref "D251") (pin "1") (pinfunction "A_1") (pintype "passive"))
      (node (ref "S251") (pin "1") (pinfunction "1_1") (pintype "passive"))
    )
    (net (code "58") (name "Net-(D252-A)") (class "Default")
      (node (ref "D252") (pin "1") (pinfunction "A_1") (pintype "passive"))
      (node (ref "S252") (pin "1") (pinfunction "1_1") (pintype "passive"))
    )
    (net (code "59") (name "Net-(D253-A)") (class "Default")
      (node (ref "D253") (pin "1") (pinfunction "A_1") (pintype "passive"))
      (node (ref "S253") (pin "1") (pinfunction "1_1") (pintype "passive"))
    )
    (net (code "60") (name "Net-(D254-A)") (class "Default")
      (node (ref "D254") (pin "1") (pinfunction "A_1") (pintype "passive"))
      (node (ref "S254") (pin "1") (pinfunction "1_1") (pintype "passive"))
    )
    (net (code "61") (name "Net-(D255-A)") (class "Default")
      (node (ref "D255") (pin "1") (pinfunction "A_1") (pintype "passive"))
      (node (ref "S255") (pin "1") (pinfunction "1_1") (pintype "passive"))
    )
    (net (code "62") (name "Net-(D256-A)") (class "Default")
      (node (ref "D256") (pin "1") (pinfunction "A_1") (pintype "passive"))
      (node (ref "S256") (pin "1") (pinfunction "1_1") (pintype "passive"))
    )
    (net (code "63") (name "Net-(D257-A)") (class "Default")
      (node (ref "D257") (pin "1") (pinfunction "A_1") (pintype "passive"))
      (node (ref "S257") (pin "1") (pinfunction "1_1") (pintype "passive"))
    )
    (net (code "64") (name "Net-(D258-A)") (class "Default")
      (node (ref "D258") (pin "1") (pinfunction "A_1") (pintype "passive"))
      (node (ref "S258") (pin "1") (pinfunction "1_1") (pintype "passive"))
    )
    (net (code "65") (name "Net-(D259-A)") (class "Default")
      (node (ref "D259") (pin "1") (pinfunction "A_1") (pintype "passive"))
      (node (ref "S259") (pin "1") (pinfunction "1_1") (pintype "passive"))
    )
    (net (code "66") (name "Net-(D260-A)") (class "Default")
      (node (ref "D260") (pin "1") (pinfunction "A_1") (pintype "passive"))
      (node (ref "S260") (pin "1") (pinfunction "1_1") (pintype "passive"))
    )
    (net (code "67") (name "Net-(D261-A)") (class "Default")
      (node (ref "D261") (pin "1") (pinfunction "A_1") (pintype "passive"))
      (node (ref "S261") (pin "1") (pinfunction "1_1") (pintype "passive"))
    )
    (net (code "68") (name "Net-(D262-A)") (class "Default")
      (node (ref "D262") (pin "1") (pinfunction "A_1") (pintype "passive"))
      (node (ref "S262") (pin "1") (pinfunction "1_1") (pintype "passive"))
    )
    (net (code "69") (name "Net-(D263-A)") (class "Default")
      (node (ref "D263") (pin "1") (pinfunction "A_1") (pintype "passive"))
      (node (ref "S263") (pin "1") (pinfunction "1_1") (pintype "passive"))
    )
    (net (code "70") (name "Net-(D264-A)") (class "Default")
      (node (ref "D264") (pin "1") (pinfunction "A_1") (pintype "passive"))
      (node (ref "S264") (pin "1") (pinfunction "1_1") (pintype "passive"))
    )
    (net (code "71") (name "Net-(D265-A)") (class "Default")
      (node (ref "D265") (pin "1") (pinfunction "A_1") (pintype "passive"))
      (node (ref "S265") (pin "1") (pinfunction "1_1") (pintype "passive"))
    )
    (net (code "72") (name "Net-(D266-A)") (class "Default")
      (node (ref "D266") (pin "1") (pinfunction "A_1") (pintype "passive"))
      (node (ref "S266") (pin "1") (pinfunction "1_1") (pintype "passive"))
    )
    (net (code "73") (name "Net-(D267-A)") (class "Default")
      (node (ref "D267") (pin "1") (pinfunction "A_1") (pintype "passive"))
      (node (ref "S267") (pin "1") (pinfunction "1_1") (pintype "passive"))
    )
    (net (code "74") (name "Net-(D268-A)") (class "Default")
      (node (ref "D268") (pin "1") (pinfunction "A_1") (pintype "passive"))
      (node (ref "S268") (pin "1") (pinfunction "1_1") (pintype "passive"))
    )
    (net (code "75") (name "Net-(D269-A)") (class "Default")
      (node (ref "D269") (pin "1") (pinfunction "A_1") (pintype "passive"))
      (node (ref "S269") (pin "1") (pinfunction "1_1") (pintype "passive"))
    )
    (net (code "76") (name "Net-(D270-A)") (class "Default")
      (node (ref "D270") (pin "1") (pinfunction "A_1") (pintype "passive"))
      (node (ref "S270") (pin "1") (pinfunction "1_1") (pintype "passive"))
    )
    (net (code "77") (name "Net-(D271-A)") (class "Default")
      (node (ref "D271") (pin "1") (pinfunction "A_1") (pintype "passive"))
      (node (ref "S271") (pin "1") (pinfunction "1_1") (pintype "passive"))
    )
    (net (code "78") (name "Net-(D272-A)") (class "Default")
      (node (ref "D272") (pin "1") (pinfunction "A_1") (pintype "passive"))
      (node (ref "S272") (pin "1") (pinfunction "1_1") (pintype "passive"))
    )
    (net (code "79") (name "Net-(D273-A)") (class "Default")
      (node (ref "D273") (pin "1") (pinfunction "A_1") (pintype "passive"))
      (node (ref "S273") (pin "1") (pinfunction "1_1") (pintype "passive"))
    )
    (net (code "80") (name "Net-(D274-A)") (class "Default")
      (node (ref "D274") (pin "1") (pinfunction "A_1") (pintype "passive"))
      (node (ref "S274") (pin "1") (pinfunction "1_1") (pintype "passive"))
    )
    (net (code "81") (name "Net-(D275-A)") (class "Default")
      (node (ref "D275") (pin "1") (pinfunction "A_1") (pintype "passive"))
      (node (ref "S275") (pin "1") (pinfunction "1_1") (pintype "passive"))
    )
    (net (code "82") (name "Net-(D276-A)") (class "Default")
      (node (ref "D276") (pin "1") (pinfunction "A_1") (pintype "passive"))
      (node (ref "S276") (pin "1") (pinfunction "1_1") (pintype "passive"))
    )
    (net (code "83") (name "Net-(D277-A)") (class "Default")
      (node (ref "D277") (pin "1") (pinfunction "A_1") (pintype "passive"))
      (node (ref "S277") (pin "1") (pinfunction "1_1") (pintype "passive"))
    )
    (net (code "84") (name "Net-(D278-A)") (class "Default")
      (node (ref "D278") (pin "1") (pinfunction "A_1") (pintype "passive"))
      (node (ref "S278") (pin "1") (pinfunction "1_1") (pintype "passive"))
    )
    (net (code "85") (name "Net-(D279-A)") (class "Default")
      (node (ref "D279") (pin "1") (pinfunction "A_1") (pintype "passive"))
      (node (ref "S279") (pin "1") (pinfunction "1_1") (pintype "passive"))
    )
    (net (code "86") (name "Net-(D280-A)") (class "Default")
      (node (ref "D280") (pin "1") (pinfunction "A_1") (pintype "passive"))
      (node (ref "S280") (pin "1") (pinfunction "1_1") (pintype "passive"))
    )
    (net (code "87") (name "Net-(D281-A)") (class "Default")
      (node (ref "D281") (pin "1") (pinfunction "A_1") (pintype "passive"))
      (node (ref "S281") (pin "1") (pinfunction "1_1") (pintype "passive"))
    )
    (net (code "88") (name "Net-(D282-A)") (class "Default")
      (node (ref "D282") (pin "1") (pinfunction "A_1") (pintype "passive"))
      (node (ref "S282") (pin "1") (pinfunction "1_1") (pintype "passive"))
    )
    (net (code "89") (name "Net-(D283-A)") (class "Default")
      (node (ref "D283") (pin "1") (pinfunction "A_1") (pintype "passive"))
      (node (ref "S283") (pin "1") (pinfunction "1_1") (pintype "passive"))
    )
    (net (code "90") (name "Net-(D284-A)") (class "Default")
      (node (ref "D284") (pin "1") (pinfunction "A_1") (pintype "passive"))
      (node (ref "S284") (pin "1") (pinfunction "1_1") (pintype "passive"))
    )
    (net (code "91") (name "Net-(D285-A)") (class "Default")
      (node (ref "D285") (pin "1") (pinfunction "A_1") (pintype "passive"))
      (node (ref "S285") (pin "1") (pinfunction "1_1") (pintype "passive"))
    )
    (net (code "92") (name "Net-(D286-A)") (class "Default")
      (node (ref "D286") (pin "1") (pinfunction "A_1") (pintype "passive"))
      (node (ref "S286") (pin "1") (pinfunction "1_1") (pintype "passive"))
    )
    (net (code "93") (name "Net-(D287-A)") (class "Default")
      (node (ref "D287") (pin "1") (pinfunction "A_1") (pintype "passive"))
      (node (ref "S287") (pin "1") (pinfunction "1_1") (pintype "passive"))
    )
    (net (code "94") (name "Net-(D288-A)") (class "Default")
      (node (ref "D288") (pin "1") (pinfunction "A_1") (pintype "passive"))
      (node (ref "S288") (pin "1") (pinfunction "1_1") (pintype "passive"))
    )
    (net (code "95") (name "Net-(D289-A)") (class "Default")
      (node (ref "D289") (pin "1") (pinfunction "A_1") (pintype "passive"))
      (node (ref "S289") (pin "1") (pinfunction "1_1") (pintype "passive"))
    )
  )
)
